# Kasli-SOC_SFP.net
KiCad netlist of a schematic drawn in Altium Designer
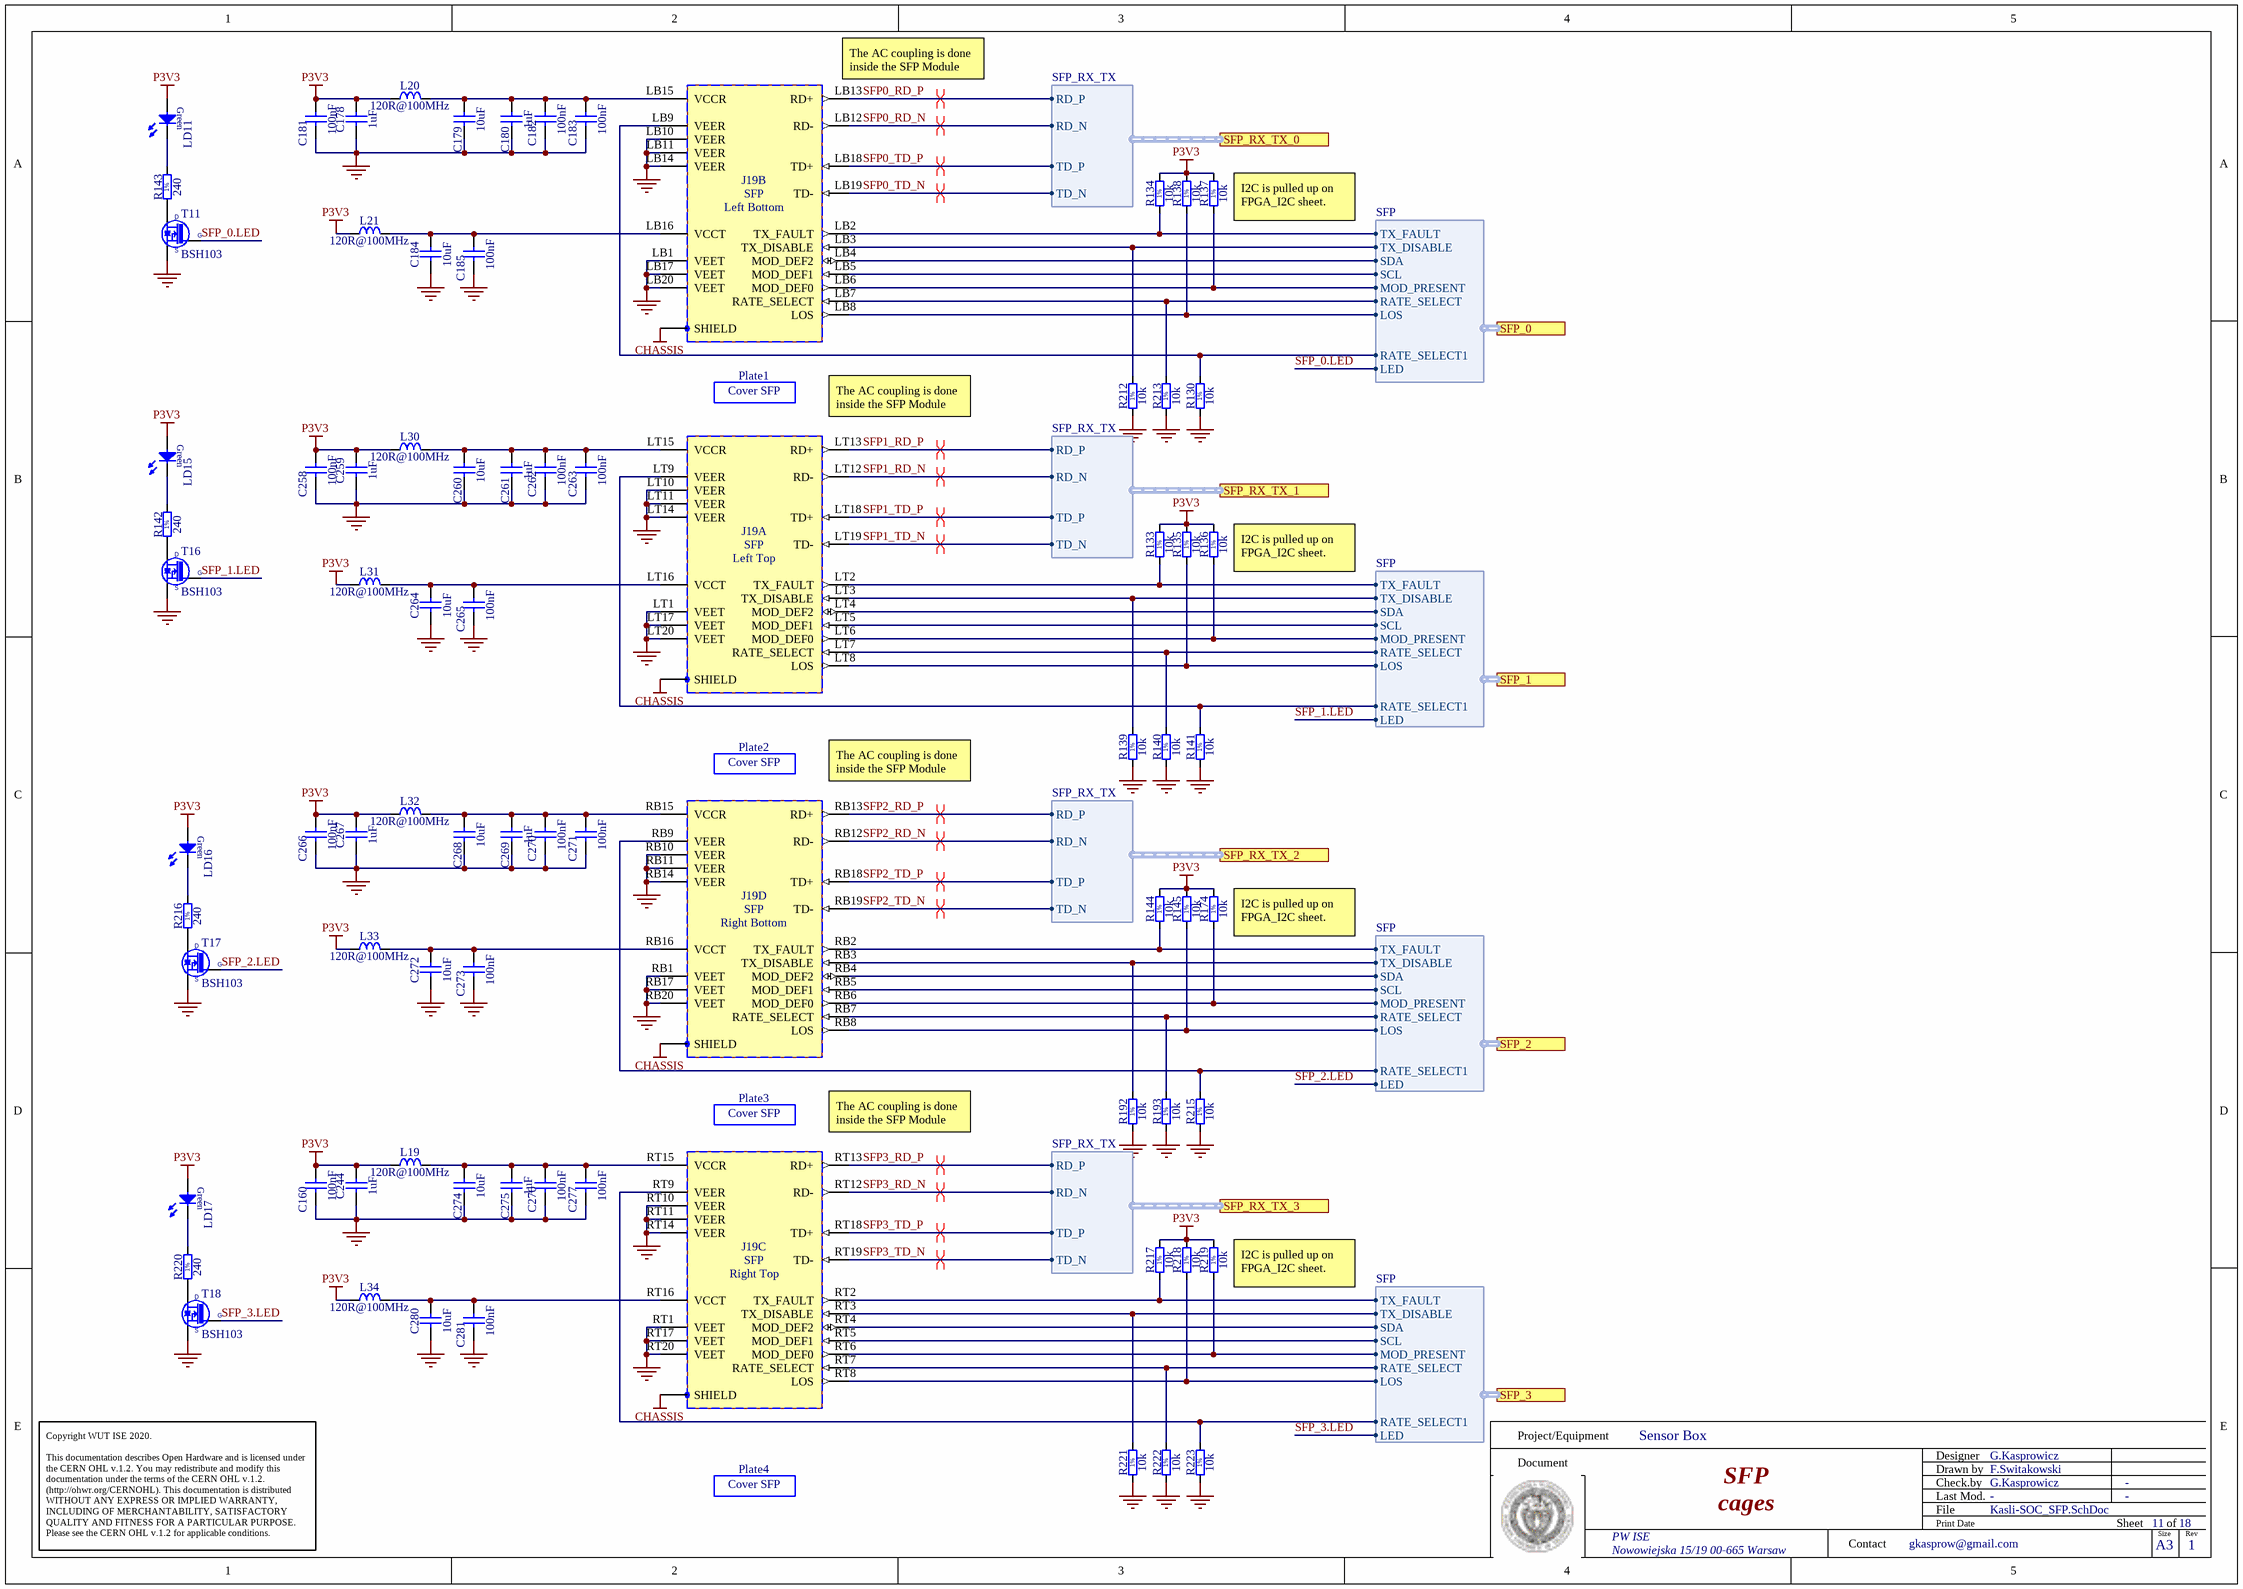
[diagram p0: Kasli-SOC_SFP.SchDoc]

(export (version "E")
  (design (tool "Eeschema 10.0.6"))
  (components
    (comp (ref "C160")
      (value "100nF")
      (footprint "CAPC1005X55N")
      (description "Non-polarised capacitor")
      (fields
        (field (name "PART NUMBER") "CC0402_100NF_16V_10%_X7R")
        (field (name "VOLTAGE") "16V")
        (field (name "AUTHOR") "CERN DEM JLC")
      )
      (libsource (lib "Capacitors") (part "Capacitor - non polarized"))
    )
    (comp (ref "C178")
      (value "1uF")
      (footprint "CAPC1005X55N")
      (description "Non-polarised capacitor")
      (fields
        (field (name "PART NUMBER") "CC0402_1UF_16V_10%_X5R")
        (field (name "VOLTAGE") "16V")
        (field (name "AUTHOR") "CERN DEM JLC")
      )
      (libsource (lib "Capacitors") (part "Capacitor - non polarized"))
    )
    (comp (ref "C179")
      (value "10uF")
      (footprint "CAPC2012X95N")
      (description "Non-polarised capacitor")
      (fields
        (field (name "PART NUMBER") "CC0805_10UF_25V_10%_X5R")
        (field (name "VOLTAGE") "25V")
        (field (name "AUTHOR") "CERN DEM JLC")
      )
      (libsource (lib "Capacitors") (part "Capacitor - non polarized"))
    )
    (comp (ref "C180")
      (value "1uF")
      (footprint "CAPC1005X55N")
      (description "Non-polarised capacitor")
      (fields
        (field (name "PART NUMBER") "CC0402_1UF_16V_10%_X5R")
        (field (name "VOLTAGE") "16V")
        (field (name "AUTHOR") "CERN DEM JLC")
      )
      (libsource (lib "Capacitors") (part "Capacitor - non polarized"))
    )
    (comp (ref "C181")
      (value "100nF")
      (footprint "CAPC1005X55N")
      (description "Non-polarised capacitor")
      (fields
        (field (name "PART NUMBER") "CC0402_100NF_16V_10%_X7R")
        (field (name "VOLTAGE") "16V")
        (field (name "AUTHOR") "CERN DEM JLC")
      )
      (libsource (lib "Capacitors") (part "Capacitor - non polarized"))
    )
    (comp (ref "C182")
      (value "100nF")
      (footprint "CAPC1005X55N")
      (description "Non-polarised capacitor")
      (fields
        (field (name "PART NUMBER") "CC0402_100NF_16V_10%_X7R")
        (field (name "VOLTAGE") "16V")
        (field (name "AUTHOR") "CERN DEM JLC")
      )
      (libsource (lib "Capacitors") (part "Capacitor - non polarized"))
    )
    (comp (ref "C183")
      (value "100nF")
      (footprint "CAPC1005X55N")
      (description "Non-polarised capacitor")
      (fields
        (field (name "PART NUMBER") "CC0402_100NF_16V_10%_X7R")
        (field (name "VOLTAGE") "16V")
        (field (name "AUTHOR") "CERN DEM JLC")
      )
      (libsource (lib "Capacitors") (part "Capacitor - non polarized"))
    )
    (comp (ref "C184")
      (value "10uF")
      (footprint "CAPC2012X95N")
      (description "Non-polarised capacitor")
      (fields
        (field (name "PART NUMBER") "CC0805_10UF_25V_10%_X5R")
        (field (name "VOLTAGE") "25V")
        (field (name "AUTHOR") "CERN DEM JLC")
      )
      (libsource (lib "Capacitors") (part "Capacitor - non polarized"))
    )
    (comp (ref "C185")
      (value "100nF")
      (footprint "CAPC1005X55N")
      (description "Non-polarised capacitor")
      (fields
        (field (name "PART NUMBER") "CC0402_100NF_16V_10%_X7R")
        (field (name "VOLTAGE") "16V")
        (field (name "AUTHOR") "CERN DEM JLC")
      )
      (libsource (lib "Capacitors") (part "Capacitor - non polarized"))
    )
    (comp (ref "C244")
      (value "1uF")
      (footprint "CAPC1005X55N")
      (description "Non-polarised capacitor")
      (fields
        (field (name "PART NUMBER") "CC0402_1UF_16V_10%_X5R")
        (field (name "VOLTAGE") "16V")
        (field (name "AUTHOR") "CERN DEM JLC")
      )
      (libsource (lib "Capacitors") (part "Capacitor - non polarized"))
    )
    (comp (ref "C258")
      (value "100nF")
      (footprint "CAPC1005X55N")
      (description "Non-polarised capacitor")
      (fields
        (field (name "PART NUMBER") "CC0402_100NF_16V_10%_X7R")
        (field (name "VOLTAGE") "16V")
        (field (name "AUTHOR") "CERN DEM JLC")
      )
      (libsource (lib "Capacitors") (part "Capacitor - non polarized"))
    )
    (comp (ref "C259")
      (value "1uF")
      (footprint "CAPC1005X55N")
      (description "Non-polarised capacitor")
      (fields
        (field (name "PART NUMBER") "CC0402_1UF_16V_10%_X5R")
        (field (name "VOLTAGE") "16V")
        (field (name "AUTHOR") "CERN DEM JLC")
      )
      (libsource (lib "Capacitors") (part "Capacitor - non polarized"))
    )
    (comp (ref "C260")
      (value "10uF")
      (footprint "CAPC2012X95N")
      (description "Non-polarised capacitor")
      (fields
        (field (name "PART NUMBER") "CC0805_10UF_25V_10%_X5R")
        (field (name "VOLTAGE") "25V")
        (field (name "AUTHOR") "CERN DEM JLC")
      )
      (libsource (lib "Capacitors") (part "Capacitor - non polarized"))
    )
    (comp (ref "C261")
      (value "1uF")
      (footprint "CAPC1005X55N")
      (description "Non-polarised capacitor")
      (fields
        (field (name "PART NUMBER") "CC0402_1UF_16V_10%_X5R")
        (field (name "VOLTAGE") "16V")
        (field (name "AUTHOR") "CERN DEM JLC")
      )
      (libsource (lib "Capacitors") (part "Capacitor - non polarized"))
    )
    (comp (ref "C262")
      (value "100nF")
      (footprint "CAPC1005X55N")
      (description "Non-polarised capacitor")
      (fields
        (field (name "PART NUMBER") "CC0402_100NF_16V_10%_X7R")
        (field (name "VOLTAGE") "16V")
        (field (name "AUTHOR") "CERN DEM JLC")
      )
      (libsource (lib "Capacitors") (part "Capacitor - non polarized"))
    )
    (comp (ref "C263")
      (value "100nF")
      (footprint "CAPC1005X55N")
      (description "Non-polarised capacitor")
      (fields
        (field (name "PART NUMBER") "CC0402_100NF_16V_10%_X7R")
        (field (name "VOLTAGE") "16V")
        (field (name "AUTHOR") "CERN DEM JLC")
      )
      (libsource (lib "Capacitors") (part "Capacitor - non polarized"))
    )
    (comp (ref "C264")
      (value "10uF")
      (footprint "CAPC2012X95N")
      (description "Non-polarised capacitor")
      (fields
        (field (name "PART NUMBER") "CC0805_10UF_25V_10%_X5R")
        (field (name "VOLTAGE") "25V")
        (field (name "AUTHOR") "CERN DEM JLC")
      )
      (libsource (lib "Capacitors") (part "Capacitor - non polarized"))
    )
    (comp (ref "C265")
      (value "100nF")
      (footprint "CAPC1005X55N")
      (description "Non-polarised capacitor")
      (fields
        (field (name "PART NUMBER") "CC0402_100NF_16V_10%_X7R")
        (field (name "VOLTAGE") "16V")
        (field (name "AUTHOR") "CERN DEM JLC")
      )
      (libsource (lib "Capacitors") (part "Capacitor - non polarized"))
    )
    (comp (ref "C266")
      (value "100nF")
      (footprint "CAPC1005X55N")
      (description "Non-polarised capacitor")
      (fields
        (field (name "PART NUMBER") "CC0402_100NF_16V_10%_X7R")
        (field (name "VOLTAGE") "16V")
        (field (name "AUTHOR") "CERN DEM JLC")
      )
      (libsource (lib "Capacitors") (part "Capacitor - non polarized"))
    )
    (comp (ref "C267")
      (value "1uF")
      (footprint "CAPC1005X55N")
      (description "Non-polarised capacitor")
      (fields
        (field (name "PART NUMBER") "CC0402_1UF_16V_10%_X5R")
        (field (name "VOLTAGE") "16V")
        (field (name "AUTHOR") "CERN DEM JLC")
      )
      (libsource (lib "Capacitors") (part "Capacitor - non polarized"))
    )
    (comp (ref "C268")
      (value "10uF")
      (footprint "CAPC2012X95N")
      (description "Non-polarised capacitor")
      (fields
        (field (name "PART NUMBER") "CC0805_10UF_25V_10%_X5R")
        (field (name "VOLTAGE") "25V")
        (field (name "AUTHOR") "CERN DEM JLC")
      )
      (libsource (lib "Capacitors") (part "Capacitor - non polarized"))
    )
    (comp (ref "C269")
      (value "1uF")
      (footprint "CAPC1005X55N")
      (description "Non-polarised capacitor")
      (fields
        (field (name "PART NUMBER") "CC0402_1UF_16V_10%_X5R")
        (field (name "VOLTAGE") "16V")
        (field (name "AUTHOR") "CERN DEM JLC")
      )
      (libsource (lib "Capacitors") (part "Capacitor - non polarized"))
    )
    (comp (ref "C270")
      (value "100nF")
      (footprint "CAPC1005X55N")
      (description "Non-polarised capacitor")
      (fields
        (field (name "PART NUMBER") "CC0402_100NF_16V_10%_X7R")
        (field (name "VOLTAGE") "16V")
        (field (name "AUTHOR") "CERN DEM JLC")
      )
      (libsource (lib "Capacitors") (part "Capacitor - non polarized"))
    )
    (comp (ref "C271")
      (value "100nF")
      (footprint "CAPC1005X55N")
      (description "Non-polarised capacitor")
      (fields
        (field (name "PART NUMBER") "CC0402_100NF_16V_10%_X7R")
        (field (name "VOLTAGE") "16V")
        (field (name "AUTHOR") "CERN DEM JLC")
      )
      (libsource (lib "Capacitors") (part "Capacitor - non polarized"))
    )
    (comp (ref "C272")
      (value "10uF")
      (footprint "CAPC2012X95N")
      (description "Non-polarised capacitor")
      (fields
        (field (name "PART NUMBER") "CC0805_10UF_25V_10%_X5R")
        (field (name "VOLTAGE") "25V")
        (field (name "AUTHOR") "CERN DEM JLC")
      )
      (libsource (lib "Capacitors") (part "Capacitor - non polarized"))
    )
    (comp (ref "C273")
      (value "100nF")
      (footprint "CAPC1005X55N")
      (description "Non-polarised capacitor")
      (fields
        (field (name "PART NUMBER") "CC0402_100NF_16V_10%_X7R")
        (field (name "VOLTAGE") "16V")
        (field (name "AUTHOR") "CERN DEM JLC")
      )
      (libsource (lib "Capacitors") (part "Capacitor - non polarized"))
    )
    (comp (ref "C274")
      (value "10uF")
      (footprint "CAPC2012X95N")
      (description "Non-polarised capacitor")
      (fields
        (field (name "PART NUMBER") "CC0805_10UF_25V_10%_X5R")
        (field (name "VOLTAGE") "25V")
        (field (name "AUTHOR") "CERN DEM JLC")
      )
      (libsource (lib "Capacitors") (part "Capacitor - non polarized"))
    )
    (comp (ref "C275")
      (value "1uF")
      (footprint "CAPC1005X55N")
      (description "Non-polarised capacitor")
      (fields
        (field (name "PART NUMBER") "CC0402_1UF_16V_10%_X5R")
        (field (name "VOLTAGE") "16V")
        (field (name "AUTHOR") "CERN DEM JLC")
      )
      (libsource (lib "Capacitors") (part "Capacitor - non polarized"))
    )
    (comp (ref "C276")
      (value "100nF")
      (footprint "CAPC1005X55N")
      (description "Non-polarised capacitor")
      (fields
        (field (name "PART NUMBER") "CC0402_100NF_16V_10%_X7R")
        (field (name "VOLTAGE") "16V")
        (field (name "AUTHOR") "CERN DEM JLC")
      )
      (libsource (lib "Capacitors") (part "Capacitor - non polarized"))
    )
    (comp (ref "C277")
      (value "100nF")
      (footprint "CAPC1005X55N")
      (description "Non-polarised capacitor")
      (fields
        (field (name "PART NUMBER") "CC0402_100NF_16V_10%_X7R")
        (field (name "VOLTAGE") "16V")
        (field (name "AUTHOR") "CERN DEM JLC")
      )
      (libsource (lib "Capacitors") (part "Capacitor - non polarized"))
    )
    (comp (ref "C280")
      (value "10uF")
      (footprint "CAPC2012X95N")
      (description "Non-polarised capacitor")
      (fields
        (field (name "PART NUMBER") "CC0805_10UF_25V_10%_X5R")
        (field (name "VOLTAGE") "25V")
        (field (name "AUTHOR") "CERN DEM JLC")
      )
      (libsource (lib "Capacitors") (part "Capacitor - non polarized"))
    )
    (comp (ref "C281")
      (value "100nF")
      (footprint "CAPC1005X55N")
      (description "Non-polarised capacitor")
      (fields
        (field (name "PART NUMBER") "CC0402_100NF_16V_10%_X7R")
        (field (name "VOLTAGE") "16V")
        (field (name "AUTHOR") "CERN DEM JLC")
      )
      (libsource (lib "Capacitors") (part "Capacitor - non polarized"))
    )
    (comp (ref "J19")
      (value "SFP")
      (footprint "AMPHENOL_UE78B212700321")
      (description "20 Position SFP  Connector (Small Form-factor Pluggable)")
      (fields
        (field (name "PART NUMBER") "AMPHENOL_UE78B212700321")
        (field (name "MANUFACTURER") "AMPHENOL")
        (field (name "AUTHOR") "CERN DEM BC")
      )
      (libsource (lib "Connectors") (part "SFP 2x2 +Cage"))
    )
    (comp (ref "L19")
      (value "120R@100MHz")
      (footprint "INDC1608X65N")
      (description "Inductor")
      (fields
        (field (name "PART NUMBER") "IND0603_MURATA_BLM18SG121TN1D")
        (field (name "POWER") "3A")
        (field (name "AUTHOR") "CERN DEM JLC")
      )
      (libsource (lib "Inductors & Transformers") (part "Inductor"))
    )
    (comp (ref "L20")
      (value "120R@100MHz")
      (footprint "INDC1608X65N")
      (description "Inductor")
      (fields
        (field (name "PART NUMBER") "IND0603_MURATA_BLM18SG121TN1D")
        (field (name "POWER") "3A")
        (field (name "AUTHOR") "CERN DEM JLC")
      )
      (libsource (lib "Inductors & Transformers") (part "Inductor"))
    )
    (comp (ref "L21")
      (value "120R@100MHz")
      (footprint "INDC1608X65N")
      (description "Inductor")
      (fields
        (field (name "PART NUMBER") "IND0603_MURATA_BLM18SG121TN1D")
        (field (name "POWER") "3A")
        (field (name "AUTHOR") "CERN DEM JLC")
      )
      (libsource (lib "Inductors & Transformers") (part "Inductor"))
    )
    (comp (ref "L30")
      (value "120R@100MHz")
      (footprint "INDC1608X65N")
      (description "Inductor")
      (fields
        (field (name "PART NUMBER") "IND0603_MURATA_BLM18SG121TN1D")
        (field (name "POWER") "3A")
        (field (name "AUTHOR") "CERN DEM JLC")
      )
      (libsource (lib "Inductors & Transformers") (part "Inductor"))
    )
    (comp (ref "L31")
      (value "120R@100MHz")
      (footprint "INDC1608X65N")
      (description "Inductor")
      (fields
        (field (name "PART NUMBER") "IND0603_MURATA_BLM18SG121TN1D")
        (field (name "POWER") "3A")
        (field (name "AUTHOR") "CERN DEM JLC")
      )
      (libsource (lib "Inductors & Transformers") (part "Inductor"))
    )
    (comp (ref "L32")
      (value "120R@100MHz")
      (footprint "INDC1608X65N")
      (description "Inductor")
      (fields
        (field (name "PART NUMBER") "IND0603_MURATA_BLM18SG121TN1D")
        (field (name "POWER") "3A")
        (field (name "AUTHOR") "CERN DEM JLC")
      )
      (libsource (lib "Inductors & Transformers") (part "Inductor"))
    )
    (comp (ref "L33")
      (value "120R@100MHz")
      (footprint "INDC1608X65N")
      (description "Inductor")
      (fields
        (field (name "PART NUMBER") "IND0603_MURATA_BLM18SG121TN1D")
        (field (name "POWER") "3A")
        (field (name "AUTHOR") "CERN DEM JLC")
      )
      (libsource (lib "Inductors & Transformers") (part "Inductor"))
    )
    (comp (ref "L34")
      (value "120R@100MHz")
      (footprint "INDC1608X65N")
      (description "Inductor")
      (fields
        (field (name "PART NUMBER") "IND0603_MURATA_BLM18SG121TN1D")
        (field (name "POWER") "3A")
        (field (name "AUTHOR") "CERN DEM JLC")
      )
      (libsource (lib "Inductors & Transformers") (part "Inductor"))
    )
    (comp (ref "LD11")
      (value "Green")
      (footprint "LED_AVAGO_HSME-C120")
      (description "LED Green 1C 2A")
      (fields
        (field (name "PART NUMBER") "LED_AVAGO_HSME-C120")
        (field (name "MANUFACTURER") "AVAGO TECHNOLOGIES")
        (field (name "AUTHOR") "CERN DEM JMW")
      )
      (libsource (lib "ICs And Semiconductors") (part "LED Green 1C 2A"))
    )
    (comp (ref "LD15")
      (value "Green")
      (footprint "LED_AVAGO_HSME-C120")
      (description "LED Green 1C 2A")
      (fields
        (field (name "PART NUMBER") "LED_AVAGO_HSME-C120")
        (field (name "MANUFACTURER") "AVAGO TECHNOLOGIES")
        (field (name "AUTHOR") "CERN DEM JMW")
      )
      (libsource (lib "ICs And Semiconductors") (part "LED Green 1C 2A"))
    )
    (comp (ref "LD16")
      (value "Green")
      (footprint "LED_AVAGO_HSME-C120")
      (description "LED Green 1C 2A")
      (fields
        (field (name "PART NUMBER") "LED_AVAGO_HSME-C120")
        (field (name "MANUFACTURER") "AVAGO TECHNOLOGIES")
        (field (name "AUTHOR") "CERN DEM JMW")
      )
      (libsource (lib "ICs And Semiconductors") (part "LED Green 1C 2A"))
    )
    (comp (ref "LD17")
      (value "Green")
      (footprint "LED_AVAGO_HSME-C120")
      (description "LED Green 1C 2A")
      (fields
        (field (name "PART NUMBER") "LED_AVAGO_HSME-C120")
        (field (name "MANUFACTURER") "AVAGO TECHNOLOGIES")
        (field (name "AUTHOR") "CERN DEM JMW")
      )
      (libsource (lib "ICs And Semiconductors") (part "LED Green 1C 2A"))
    )
    (comp (ref "Plate1")
      (value "Cover SFP")
      (footprint "AMPHENOL_U77A11108000P")
      (description "Plastic Dust Cover SFP Cage")
      (fields
        (field (name "PART NUMBER") "AMPHENOL_U77A11108000P")
        (field (name "MANUFACTURER") "AMPHENOL")
        (field (name "AUTHOR") "CERN DEM BC")
      )
      (libsource (lib "Eletro-mechanical") (part "SFP Cover No Pin"))
    )
    (comp (ref "Plate2")
      (value "Cover SFP")
      (footprint "AMPHENOL_U77A11108000P")
      (description "Plastic Dust Cover SFP Cage")
      (fields
        (field (name "MANUFACTURER") "AMPHENOL")
        (field (name "MANUFACTURER PART NUMBER") "U77A11108000P")
        (field (name "AUTHOR") "CERN DEM BC")
      )
      (libsource (lib "Eletro-mechanical") (part "SFP Cover No Pin"))
    )
    (comp (ref "Plate3")
      (value "Cover SFP")
      (footprint "AMPHENOL_U77A11108000P")
      (description "Plastic Dust Cover SFP Cage")
      (fields
        (field (name "MANUFACTURER") "AMPHENOL")
        (field (name "MANUFACTURER PART NUMBER") "U77A11108000P")
        (field (name "AUTHOR") "CERN DEM BC")
      )
      (libsource (lib "Eletro-mechanical") (part "SFP Cover No Pin"))
    )
    (comp (ref "Plate4")
      (value "Cover SFP")
      (footprint "AMPHENOL_U77A11108000P")
      (description "Plastic Dust Cover SFP Cage")
      (fields
        (field (name "MANUFACTURER") "AMPHENOL")
        (field (name "MANUFACTURER PART NUMBER") "U77A11108000P")
        (field (name "AUTHOR") "CERN DEM BC")
      )
      (libsource (lib "Eletro-mechanical") (part "SFP Cover No Pin"))
    )
    (comp (ref "R130")
      (value "10k")
      (footprint "RESC1005X40N")
      (description "Resistor - 1%")
      (fields
        (field (name "PART NUMBER") "R0402_10K_1%_0.0625W_100PPM")
        (field (name "POWER") "0.0625W")
        (field (name "AUTHOR") "CERN DEM JLC")
      )
      (libsource (lib "Resistors") (part "Resistor - 1%"))
    )
    (comp (ref "R133")
      (value "10k")
      (footprint "RESC1005X40N")
      (description "Resistor - 1%")
      (fields
        (field (name "PART NUMBER") "R0402_10K_1%_0.0625W_100PPM")
        (field (name "POWER") "0.0625W")
        (field (name "AUTHOR") "CERN DEM JLC")
      )
      (libsource (lib "Resistors") (part "Resistor - 1%"))
    )
    (comp (ref "R134")
      (value "10k")
      (footprint "RESC1005X40N")
      (description "Resistor - 1%")
      (fields
        (field (name "PART NUMBER") "R0402_10K_1%_0.0625W_100PPM")
        (field (name "POWER") "0.0625W")
        (field (name "AUTHOR") "CERN DEM JLC")
      )
      (libsource (lib "Resistors") (part "Resistor - 1%"))
    )
    (comp (ref "R135")
      (value "10k")
      (footprint "RESC1005X40N")
      (description "Resistor - 1%")
      (fields
        (field (name "PART NUMBER") "R0402_10K_1%_0.0625W_100PPM")
        (field (name "POWER") "0.0625W")
        (field (name "AUTHOR") "CERN DEM JLC")
      )
      (libsource (lib "Resistors") (part "Resistor - 1%"))
    )
    (comp (ref "R136")
      (value "10k")
      (footprint "RESC1005X40N")
      (description "Resistor - 1%")
      (fields
        (field (name "PART NUMBER") "R0402_10K_1%_0.0625W_100PPM")
        (field (name "POWER") "0.0625W")
        (field (name "AUTHOR") "CERN DEM JLC")
      )
      (libsource (lib "Resistors") (part "Resistor - 1%"))
    )
    (comp (ref "R137")
      (value "10k")
      (footprint "RESC1005X40N")
      (description "Resistor - 1%")
      (fields
        (field (name "PART NUMBER") "R0402_10K_1%_0.0625W_100PPM")
        (field (name "POWER") "0.0625W")
        (field (name "AUTHOR") "CERN DEM JLC")
      )
      (libsource (lib "Resistors") (part "Resistor - 1%"))
    )
    (comp (ref "R138")
      (value "10k")
      (footprint "RESC1005X40N")
      (description "Resistor - 1%")
      (fields
        (field (name "PART NUMBER") "R0402_10K_1%_0.0625W_100PPM")
        (field (name "POWER") "0.0625W")
        (field (name "AUTHOR") "CERN DEM JLC")
      )
      (libsource (lib "Resistors") (part "Resistor - 1%"))
    )
    (comp (ref "R139")
      (value "10k")
      (footprint "RESC1005X40N")
      (description "Resistor - 1%")
      (fields
        (field (name "PART NUMBER") "R0402_10K_1%_0.0625W_100PPM")
        (field (name "POWER") "0.0625W")
        (field (name "AUTHOR") "CERN DEM JLC")
      )
      (libsource (lib "Resistors") (part "Resistor - 1%"))
    )
    (comp (ref "R140")
      (value "10k")
      (footprint "RESC1005X40N")
      (description "Resistor - 1%")
      (fields
        (field (name "PART NUMBER") "R0402_10K_1%_0.0625W_100PPM")
        (field (name "POWER") "0.0625W")
        (field (name "AUTHOR") "CERN DEM JLC")
      )
      (libsource (lib "Resistors") (part "Resistor - 1%"))
    )
    (comp (ref "R141")
      (value "10k")
      (footprint "RESC1005X40N")
      (description "Resistor - 1%")
      (fields
        (field (name "PART NUMBER") "R0402_10K_1%_0.0625W_100PPM")
        (field (name "POWER") "0.0625W")
        (field (name "AUTHOR") "CERN DEM JLC")
      )
      (libsource (lib "Resistors") (part "Resistor - 1%"))
    )
    (comp (ref "R142")
      (value "240")
      (footprint "RESC1005X40N")
      (description "Resistor - 1%")
      (fields
        (field (name "PART NUMBER") "R0402_240R_1%_0.0625W_100PPM")
        (field (name "POWER") "0.0625W")
        (field (name "AUTHOR") "CERN DEM JLC")
      )
      (libsource (lib "Resistors") (part "Resistor - 1%"))
    )
    (comp (ref "R143")
      (value "240")
      (footprint "RESC1005X40N")
      (description "Resistor - 1%")
      (fields
        (field (name "PART NUMBER") "R0402_240R_1%_0.0625W_100PPM")
        (field (name "POWER") "0.0625W")
        (field (name "AUTHOR") "CERN DEM JLC")
      )
      (libsource (lib "Resistors") (part "Resistor - 1%"))
    )
    (comp (ref "R144")
      (value "10k")
      (footprint "RESC1005X40N")
      (description "Resistor - 1%")
      (fields
        (field (name "PART NUMBER") "R0402_10K_1%_0.0625W_100PPM")
        (field (name "POWER") "0.0625W")
        (field (name "AUTHOR") "CERN DEM JLC")
      )
      (libsource (lib "Resistors") (part "Resistor - 1%"))
    )
    (comp (ref "R145")
      (value "10k")
      (footprint "RESC1005X40N")
      (description "Resistor - 1%")
      (fields
        (field (name "PART NUMBER") "R0402_10K_1%_0.0625W_100PPM")
        (field (name "POWER") "0.0625W")
        (field (name "AUTHOR") "CERN DEM JLC")
      )
      (libsource (lib "Resistors") (part "Resistor - 1%"))
    )
    (comp (ref "R174")
      (value "10k")
      (footprint "RESC1005X40N")
      (description "Resistor - 1%")
      (fields
        (field (name "PART NUMBER") "R0402_10K_1%_0.0625W_100PPM")
        (field (name "POWER") "0.0625W")
        (field (name "AUTHOR") "CERN DEM JLC")
      )
      (libsource (lib "Resistors") (part "Resistor - 1%"))
    )
    (comp (ref "R192")
      (value "10k")
      (footprint "RESC1005X40N")
      (description "Resistor - 1%")
      (fields
        (field (name "PART NUMBER") "R0402_10K_1%_0.0625W_100PPM")
        (field (name "POWER") "0.0625W")
        (field (name "AUTHOR") "CERN DEM JLC")
      )
      (libsource (lib "Resistors") (part "Resistor - 1%"))
    )
    (comp (ref "R193")
      (value "10k")
      (footprint "RESC1005X40N")
      (description "Resistor - 1%")
      (fields
        (field (name "PART NUMBER") "R0402_10K_1%_0.0625W_100PPM")
        (field (name "POWER") "0.0625W")
        (field (name "AUTHOR") "CERN DEM JLC")
      )
      (libsource (lib "Resistors") (part "Resistor - 1%"))
    )
    (comp (ref "R212")
      (value "10k")
      (footprint "RESC1005X40N")
      (description "Resistor - 1%")
      (fields
        (field (name "PART NUMBER") "R0402_10K_1%_0.0625W_100PPM")
        (field (name "POWER") "0.0625W")
        (field (name "AUTHOR") "CERN DEM JLC")
      )
      (libsource (lib "Resistors") (part "Resistor - 1%"))
    )
    (comp (ref "R213")
      (value "10k")
      (footprint "RESC1005X40N")
      (description "Resistor - 1%")
      (fields
        (field (name "PART NUMBER") "R0402_10K_1%_0.0625W_100PPM")
        (field (name "POWER") "0.0625W")
        (field (name "AUTHOR") "CERN DEM JLC")
      )
      (libsource (lib "Resistors") (part "Resistor - 1%"))
    )
    (comp (ref "R215")
      (value "10k")
      (footprint "RESC1005X40N")
      (description "Resistor - 1%")
      (fields
        (field (name "PART NUMBER") "R0402_10K_1%_0.0625W_100PPM")
        (field (name "POWER") "0.0625W")
        (field (name "AUTHOR") "CERN DEM JLC")
      )
      (libsource (lib "Resistors") (part "Resistor - 1%"))
    )
    (comp (ref "R216")
      (value "240")
      (footprint "RESC1005X40N")
      (description "Resistor - 1%")
      (fields
        (field (name "PART NUMBER") "R0402_240R_1%_0.0625W_100PPM")
        (field (name "POWER") "0.0625W")
        (field (name "AUTHOR") "CERN DEM JLC")
      )
      (libsource (lib "Resistors") (part "Resistor - 1%"))
    )
    (comp (ref "R217")
      (value "10k")
      (footprint "RESC1005X40N")
      (description "Resistor - 1%")
      (fields
        (field (name "PART NUMBER") "R0402_10K_1%_0.0625W_100PPM")
        (field (name "POWER") "0.0625W")
        (field (name "AUTHOR") "CERN DEM JLC")
      )
      (libsource (lib "Resistors") (part "Resistor - 1%"))
    )
    (comp (ref "R218")
      (value "10k")
      (footprint "RESC1005X40N")
      (description "Resistor - 1%")
      (fields
        (field (name "PART NUMBER") "R0402_10K_1%_0.0625W_100PPM")
        (field (name "POWER") "0.0625W")
        (field (name "AUTHOR") "CERN DEM JLC")
      )
      (libsource (lib "Resistors") (part "Resistor - 1%"))
    )
    (comp (ref "R219")
      (value "10k")
      (footprint "RESC1005X40N")
      (description "Resistor - 1%")
      (fields
        (field (name "PART NUMBER") "R0402_10K_1%_0.0625W_100PPM")
        (field (name "POWER") "0.0625W")
        (field (name "AUTHOR") "CERN DEM JLC")
      )
      (libsource (lib "Resistors") (part "Resistor - 1%"))
    )
    (comp (ref "R220")
      (value "240")
      (footprint "RESC1005X40N")
      (description "Resistor - 1%")
      (fields
        (field (name "PART NUMBER") "R0402_240R_1%_0.0625W_100PPM")
        (field (name "POWER") "0.0625W")
        (field (name "AUTHOR") "CERN DEM JLC")
      )
      (libsource (lib "Resistors") (part "Resistor - 1%"))
    )
    (comp (ref "R221")
      (value "10k")
      (footprint "RESC1005X40N")
      (description "Resistor - 1%")
      (fields
        (field (name "PART NUMBER") "R0402_10K_1%_0.0625W_100PPM")
        (field (name "POWER") "0.0625W")
        (field (name "AUTHOR") "CERN DEM JLC")
      )
      (libsource (lib "Resistors") (part "Resistor - 1%"))
    )
    (comp (ref "R222")
      (value "10k")
      (footprint "RESC1005X40N")
      (description "Resistor - 1%")
      (fields
        (field (name "PART NUMBER") "R0402_10K_1%_0.0625W_100PPM")
        (field (name "POWER") "0.0625W")
        (field (name "AUTHOR") "CERN DEM JLC")
      )
      (libsource (lib "Resistors") (part "Resistor - 1%"))
    )
    (comp (ref "R223")
      (value "10k")
      (footprint "RESC1005X40N")
      (description "Resistor - 1%")
      (fields
        (field (name "PART NUMBER") "R0402_10K_1%_0.0625W_100PPM")
        (field (name "POWER") "0.0625W")
        (field (name "AUTHOR") "CERN DEM JLC")
      )
      (libsource (lib "Resistors") (part "Resistor - 1%"))
    )
    (comp (ref "T11")
      (value "BSH103")
      (footprint "SOT95P230X110-3N")
      (description "N-CHANNEL MOSFET WITH DIODE")
      (fields (field (name "MANUFACTURER") "NEXPERIA") (field (name "AUTHOR") "CERN DEM JLC"))
      (libsource (lib "ICs And Semiconductors") (part "N-MOSFET-D 1G 2S 3D"))
    )
    (comp (ref "T16")
      (value "BSH103")
      (footprint "SOT95P230X110-3N")
      (description "N-CHANNEL MOSFET WITH DIODE")
      (fields (field (name "MANUFACTURER") "NEXPERIA") (field (name "AUTHOR") "CERN DEM JLC"))
      (libsource (lib "ICs And Semiconductors") (part "N-MOSFET-D 1G 2S 3D"))
    )
    (comp (ref "T17")
      (value "BSH103")
      (footprint "SOT95P230X110-3N")
      (description "N-CHANNEL MOSFET WITH DIODE")
      (fields (field (name "MANUFACTURER") "NEXPERIA") (field (name "AUTHOR") "CERN DEM JLC"))
      (libsource (lib "ICs And Semiconductors") (part "N-MOSFET-D 1G 2S 3D"))
    )
    (comp (ref "T18")
      (value "BSH103")
      (footprint "SOT95P230X110-3N")
      (description "N-CHANNEL MOSFET WITH DIODE")
      (fields (field (name "MANUFACTURER") "NEXPERIA") (field (name "AUTHOR") "CERN DEM JLC"))
      (libsource (lib "ICs And Semiconductors") (part "N-MOSFET-D 1G 2S 3D"))
    )
  )
  (nets
    (net (code "3") (name "/SFP0_RD_N") (class "Default")
      (node (ref "J19") (pin "LB12") (pinfunction "RD-_LB12") (pintype "output"))
    )
    (net (code "4") (name "/SFP0_RD_P") (class "Default")
      (node (ref "J19") (pin "LB13") (pinfunction "RD+_LB13") (pintype "output"))
    )
    (net (code "5") (name "/SFP0_TD_N") (class "Default")
      (node (ref "J19") (pin "LB19") (pinfunction "TD-_LB19") (pintype "input"))
    )
    (net (code "6") (name "/SFP0_TD_P") (class "Default")
      (node (ref "J19") (pin "LB18") (pinfunction "TD+_LB18") (pintype "input"))
    )
    (net (code "7") (name "/SFP1_RD_N") (class "Default")
      (node (ref "J19") (pin "LT12") (pinfunction "RD-_LT12") (pintype "output"))
    )
    (net (code "8") (name "/SFP1_RD_P") (class "Default")
      (node (ref "J19") (pin "LT13") (pinfunction "RD+_LT13") (pintype "output"))
    )
    (net (code "9") (name "/SFP1_TD_N") (class "Default")
      (node (ref "J19") (pin "LT19") (pinfunction "TD-_LT19") (pintype "input"))
    )
    (net (code "10") (name "/SFP1_TD_P") (class "Default")
      (node (ref "J19") (pin "LT18") (pinfunction "TD+_LT18") (pintype "input"))
    )
    (net (code "11") (name "/SFP2_RD_N") (class "Default")
      (node (ref "J19") (pin "RB12") (pinfunction "RD-_RB12") (pintype "output"))
    )
    (net (code "12") (name "/SFP2_RD_P") (class "Default")
      (node (ref "J19") (pin "RB13") (pinfunction "RD+_RB13") (pintype "output"))
    )
    (net (code "13") (name "/SFP2_TD_N") (class "Default")
      (node (ref "J19") (pin "RB19") (pinfunction "TD-_RB19") (pintype "input"))
    )
    (net (code "14") (name "/SFP2_TD_P") (class "Default")
      (node (ref "J19") (pin "RB18") (pinfunction "TD+_RB18") (pintype "input"))
    )
    (net (code "15") (name "/SFP3_RD_N") (class "Default")
      (node (ref "J19") (pin "RT12") (pinfunction "RD-_RT12") (pintype "output"))
    )
    (net (code "16") (name "/SFP3_RD_P") (class "Default")
      (node (ref "J19") (pin "RT13") (pinfunction "RD+_RT13") (pintype "output"))
    )
    (net (code "17") (name "/SFP3_TD_N") (class "Default")
      (node (ref "J19") (pin "RT19") (pinfunction "TD-_RT19") (pintype "input"))
    )
    (net (code "18") (name "/SFP3_TD_P") (class "Default")
      (node (ref "J19") (pin "RT18") (pinfunction "TD+_RT18") (pintype "input"))
    )
    (net (code "19") (name "/SFP_0.LED") (class "Default")
      (node (ref "T11") (pin "1") (pinfunction "G_1") (pintype "passive"))
    )
    (net (code "20") (name "/SFP_1.LED") (class "Default")
      (node (ref "T16") (pin "1") (pinfunction "G_1") (pintype "passive"))
    )
    (net (code "21") (name "/SFP_2.LED") (class "Default")
      (node (ref "T17") (pin "1") (pinfunction "G_1") (pintype "passive"))
    )
    (net (code "22") (name "/SFP_3.LED") (class "Default")
      (node (ref "T18") (pin "1") (pinfunction "G_1") (pintype "passive"))
    )
    (net (code "25") (name "CHASSIS") (class "Default")
      (node (ref "J19") (pin "SHIELD") (pinfunction "SHIELD_SHIELD") (pintype "power_in"))
    )
    (net (code "26") (name "GND") (class "Default")
      (node (ref "C160") (pin "1") (pinfunction "1_1") (pintype "passive"))
      (node (ref "C178") (pin "1") (pinfunction "1_1") (pintype "passive"))
      (node (ref "C179") (pin "1") (pinfunction "1_1") (pintype "passive"))
      (node (ref "C180") (pin "1") (pinfunction "1_1") (pintype "passive"))
      (node (ref "C181") (pin "1") (pinfunction "1_1") (pintype "passive"))
      (node (ref "C182") (pin "1") (pinfunction "1_1") (pintype "passive"))
      (node (ref "C183") (pin "1") (pinfunction "1_1") (pintype "passive"))
      (node (ref "C184") (pin "1") (pinfunction "1_1") (pintype "passive"))
      (node (ref "C185") (pin "1") (pinfunction "1_1") (pintype "passive"))
      (node (ref "C244") (pin "1") (pinfunction "1_1") (pintype "passive"))
      (node (ref "C258") (pin "1") (pinfunction "1_1") (pintype "passive"))
      (node (ref "C259") (pin "1") (pinfunction "1_1") (pintype "passive"))
      (node (ref "C260") (pin "1") (pinfunction "1_1") (pintype "passive"))
      (node (ref "C261") (pin "1") (pinfunction "1_1") (pintype "passive"))
      (node (ref "C262") (pin "1") (pinfunction "1_1") (pintype "passive"))
      (node (ref "C263") (pin "1") (pinfunction "1_1") (pintype "passive"))
      (node (ref "C264") (pin "1") (pinfunction "1_1") (pintype "passive"))
      (node (ref "C265") (pin "1") (pinfunction "1_1") (pintype "passive"))
      (node (ref "C266") (pin "1") (pinfunction "1_1") (pintype "passive"))
      (node (ref "C267") (pin "1") (pinfunction "1_1") (pintype "passive"))
      (node (ref "C268") (pin "1") (pinfunction "1_1") (pintype "passive"))
      (node (ref "C269") (pin "1") (pinfunction "1_1") (pintype "passive"))
      (node (ref "C270") (pin "1") (pinfunction "1_1") (pintype "passive"))
      (node (ref "C271") (pin "1") (pinfunction "1_1") (pintype "passive"))
      (node (ref "C272") (pin "1") (pinfunction "1_1") (pintype "passive"))
      (node (ref "C273") (pin "1") (pinfunction "1_1") (pintype "passive"))
      (node (ref "C274") (pin "1") (pinfunction "1_1") (pintype "passive"))
      (node (ref "C275") (pin "1") (pinfunction "1_1") (pintype "passive"))
      (node (ref "C276") (pin "1") (pinfunction "1_1") (pintype "passive"))
      (node (ref "C277") (pin "1") (pinfunction "1_1") (pintype "passive"))
      (node (ref "C280") (pin "1") (pinfunction "1_1") (pintype "passive"))
      (node (ref "C281") (pin "1") (pinfunction "1_1") (pintype "passive"))
      (node (ref "J19") (pin "LB1") (pinfunction "VEET_LB1") (pintype "power_in"))
      (node (ref "J19") (pin "LB10") (pinfunction "VEER_LB10") (pintype "power_in"))
      (node (ref "J19") (pin "LB11") (pinfunction "VEER_LB11") (pintype "power_in"))
      (node (ref "J19") (pin "LB14") (pinfunction "VEER_LB14") (pintype "power_in"))
      (node (ref "J19") (pin "LB17") (pinfunction "VEET_LB17") (pintype "power_in"))
      (node (ref "J19") (pin "LB20") (pinfunction "VEET_LB20") (pintype "power_in"))
      (node (ref "J19") (pin "LT1") (pinfunction "VEET_LT1") (pintype "power_in"))
      (node (ref "J19") (pin "LT10") (pinfunction "VEER_LT10") (pintype "power_in"))
      (node (ref "J19") (pin "LT11") (pinfunction "VEER_LT11") (pintype "power_in"))
      (node (ref "J19") (pin "LT14") (pinfunction "VEER_LT14") (pintype "power_in"))
      (node (ref "J19") (pin "LT17") (pinfunction "VEET_LT17") (pintype "power_in"))
      (node (ref "J19") (pin "LT20") (pinfunction "VEET_LT20") (pintype "power_in"))
      (node (ref "J19") (pin "RB1") (pinfunction "VEET_RB1") (pintype "power_in"))
      (node (ref "J19") (pin "RB10") (pinfunction "VEER_RB10") (pintype "power_in"))
      (node (ref "J19") (pin "RB11") (pinfunction "VEER_RB11") (pintype "power_in"))
      (node (ref "J19") (pin "RB14") (pinfunction "VEER_RB14") (pintype "power_in"))
      (node (ref "J19") (pin "RB17") (pinfunction "VEET_RB17") (pintype "power_in"))
      (node (ref "J19") (pin "RB20") (pinfunction "VEET_RB20") (pintype "power_in"))
      (node (ref "J19") (pin "RT1") (pinfunction "VEET_RT1") (pintype "power_in"))
      (node (ref "J19") (pin "RT10") (pinfunction "VEER_RT10") (pintype "power_in"))
      (node (ref "J19") (pin "RT11") (pinfunction "VEER_RT11") (pintype "power_in"))
      (node (ref "J19") (pin "RT14") (pinfunction "VEER_RT14") (pintype "power_in"))
      (node (ref "J19") (pin "RT17") (pinfunction "VEET_RT17") (pintype "power_in"))
      (node (ref "J19") (pin "RT20") (pinfunction "VEET_RT20") (pintype "power_in"))
      (node (ref "R130") (pin "1") (pinfunction "1_1") (pintype "passive"))
      (node (ref "R139") (pin "1") (pinfunction "1_1") (pintype "passive"))
      (node (ref "R140") (pin "1") (pinfunction "1_1") (pintype "passive"))
      (node (ref "R141") (pin "1") (pinfunction "1_1") (pintype "passive"))
      (node (ref "R192") (pin "1") (pinfunction "1_1") (pintype "passive"))
      (node (ref "R193") (pin "1") (pinfunction "1_1") (pintype "passive"))
      (node (ref "R212") (pin "1") (pinfunction "1_1") (pintype "passive"))
      (node (ref "R213") (pin "1") (pinfunction "1_1") (pintype "passive"))
      (node (ref "R215") (pin "1") (pinfunction "1_1") (pintype "passive"))
      (node (ref "R221") (pin "1") (pinfunction "1_1") (pintype "passive"))
      (node (ref "R222") (pin "1") (pinfunction "1_1") (pintype "passive"))
      (node (ref "R223") (pin "1") (pinfunction "1_1") (pintype "passive"))
      (node (ref "T11") (pin "2") (pinfunction "S_2") (pintype "passive"))
      (node (ref "T16") (pin "2") (pinfunction "S_2") (pintype "passive"))
      (node (ref "T17") (pin "2") (pinfunction "S_2") (pintype "passive"))
      (node (ref "T18") (pin "2") (pinfunction "S_2") (pintype "passive"))
    )
    (net (code "27") (name "Net-(J19A-LOS)") (class "Default")
      (node (ref "J19") (pin "LT8") (pinfunction "LOS_LT8") (pintype "output"))
      (node (ref "R135") (pin "1") (pinfunction "1_1") (pintype "passive"))
    )
    (net (code "28") (name "Net-(J19A-MOD_DEF0)") (class "Default")
      (node (ref "J19") (pin "LT6") (pinfunction "MOD_DEF0_LT6") (pintype "output"))
      (node (ref "R136") (pin "1") (pinfunction "1_1") (pintype "passive"))
    )
    (net (code "29") (name "Net-(J19A-RATE_SELECT)") (class "Default")
      (node (ref "J19") (pin "LT7") (pinfunction "RATE_SELECT_LT7") (pintype "input"))
      (node (ref "R140") (pin "2") (pinfunction "2_2") (pintype "passive"))
    )
    (net (code "30") (name "Net-(J19A-TX_DISABLE)") (class "Default")
      (node (ref "J19") (pin "LT3") (pinfunction "TX_DISABLE_LT3") (pintype "input"))
      (node (ref "R139") (pin "2") (pinfunction "2_2") (pintype "passive"))
    )
    (net (code "31") (name "Net-(J19A-TX_FAULT)") (class "Default")
      (node (ref "J19") (pin "LT2") (pinfunction "TX_FAULT_LT2") (pintype "output"))
      (node (ref "R133") (pin "1") (pinfunction "1_1") (pintype "passive"))
    )
    (net (code "32") (name "Net-(J19A-VCCR)") (class "Default")
      (node (ref "C260") (pin "2") (pinfunction "2_2") (pintype "passive"))
      (node (ref "C261") (pin "2") (pinfunction "2_2") (pintype "passive"))
      (node (ref "C262") (pin "2") (pinfunction "2_2") (pintype "passive"))
      (node (ref "C263") (pin "2") (pinfunction "2_2") (pintype "passive"))
      (node (ref "J19") (pin "LT15") (pinfunction "VCCR_LT15") (pintype "power_in"))
      (node (ref "L30") (pin "2") (pinfunction "2_2") (pintype "passive"))
    )
    (net (code "33") (name "Net-(J19A-VCCT)") (class "Default")
      (node (ref "C264") (pin "2") (pinfunction "2_2") (pintype "passive"))
      (node (ref "C265") (pin "2") (pinfunction "2_2") (pintype "passive"))
      (node (ref "J19") (pin "LT16") (pinfunction "VCCT_LT16") (pintype "power_in"))
      (node (ref "L31") (pin "2") (pinfunction "2_2") (pintype "passive"))
    )
    (net (code "34") (name "Net-(J19A-VEER-PadLT9)") (class "Default")
      (node (ref "J19") (pin "LT9") (pinfunction "VEER_LT9") (pintype "power_in"))
      (node (ref "R141") (pin "2") (pinfunction "2_2") (pintype "passive"))
    )
    (net (code "35") (name "Net-(J19B-LOS)") (class "Default")
      (node (ref "J19") (pin "LB8") (pinfunction "LOS_LB8") (pintype "output"))
      (node (ref "R138") (pin "1") (pinfunction "1_1") (pintype "passive"))
    )
    (net (code "36") (name "Net-(J19B-MOD_DEF0)") (class "Default")
      (node (ref "J19") (pin "LB6") (pinfunction "MOD_DEF0_LB6") (pintype "output"))
      (node (ref "R137") (pin "1") (pinfunction "1_1") (pintype "passive"))
    )
    (net (code "37") (name "Net-(J19B-RATE_SELECT)") (class "Default")
      (node (ref "J19") (pin "LB7") (pinfunction "RATE_SELECT_LB7") (pintype "input"))
      (node (ref "R213") (pin "2") (pinfunction "2_2") (pintype "passive"))
    )
    (net (code "38") (name "Net-(J19B-TX_DISABLE)") (class "Default")
      (node (ref "J19") (pin "LB3") (pinfunction "TX_DISABLE_LB3") (pintype "input"))
      (node (ref "R212") (pin "2") (pinfunction "2_2") (pintype "passive"))
    )
    (net (code "39") (name "Net-(J19B-TX_FAULT)") (class "Default")
      (node (ref "J19") (pin "LB2") (pinfunction "TX_FAULT_LB2") (pintype "output"))
      (node (ref "R134") (pin "1") (pinfunction "1_1") (pintype "passive"))
    )
    (net (code "40") (name "Net-(J19B-VCCR)") (class "Default")
      (node (ref "C179") (pin "2") (pinfunction "2_2") (pintype "passive"))
      (node (ref "C180") (pin "2") (pinfunction "2_2") (pintype "passive"))
      (node (ref "C182") (pin "2") (pinfunction "2_2") (pintype "passive"))
      (node (ref "C183") (pin "2") (pinfunction "2_2") (pintype "passive"))
      (node (ref "J19") (pin "LB15") (pinfunction "VCCR_LB15") (pintype "power_in"))
      (node (ref "L20") (pin "2") (pinfunction "2_2") (pintype "passive"))
    )
    (net (code "41") (name "Net-(J19B-VCCT)") (class "Default")
      (node (ref "C184") (pin "2") (pinfunction "2_2") (pintype "passive"))
      (node (ref "C185") (pin "2") (pinfunction "2_2") (pintype "passive"))
      (node (ref "J19") (pin "LB16") (pinfunction "VCCT_LB16") (pintype "power_in"))
      (node (ref "L21") (pin "2") (pinfunction "2_2") (pintype "passive"))
    )
    (net (code "42") (name "Net-(J19B-VEER-PadLB9)") (class "Default")
      (node (ref "J19") (pin "LB9") (pinfunction "VEER_LB9") (pintype "power_in"))
      (node (ref "R130") (pin "2") (pinfunction "2_2") (pintype "passive"))
    )
    (net (code "43") (name "Net-(J19C-LOS)") (class "Default")
      (node (ref "J19") (pin "RT8") (pinfunction "LOS_RT8") (pintype "output"))
      (node (ref "R218") (pin "1") (pinfunction "1_1") (pintype "passive"))
    )
    (net (code "44") (name "Net-(J19C-MOD_DEF0)") (class "Default")
      (node (ref "J19") (pin "RT6") (pinfunction "MOD_DEF0_RT6") (pintype "output"))
      (node (ref "R219") (pin "1") (pinfunction "1_1") (pintype "passive"))
    )
    (net (code "45") (name "Net-(J19C-RATE_SELECT)") (class "Default")
      (node (ref "J19") (pin "RT7") (pinfunction "RATE_SELECT_RT7") (pintype "input"))
      (node (ref "R222") (pin "2") (pinfunction "2_2") (pintype "passive"))
    )
    (net (code "46") (name "Net-(J19C-TX_DISABLE)") (class "Default")
      (node (ref "J19") (pin "RT3") (pinfunction "TX_DISABLE_RT3") (pintype "input"))
      (node (ref "R221") (pin "2") (pinfunction "2_2") (pintype "passive"))
    )
    (net (code "47") (name "Net-(J19C-TX_FAULT)") (class "Default")
      (node (ref "J19") (pin "RT2") (pinfunction "TX_FAULT_RT2") (pintype "output"))
      (node (ref "R217") (pin "1") (pinfunction "1_1") (pintype "passive"))
    )
    (net (code "48") (name "Net-(J19C-VCCR)") (class "Default")
      (node (ref "C274") (pin "2") (pinfunction "2_2") (pintype "passive"))
      (node (ref "C275") (pin "2") (pinfunction "2_2") (pintype "passive"))
      (node (ref "C276") (pin "2") (pinfunction "2_2") (pintype "passive"))
      (node (ref "C277") (pin "2") (pinfunction "2_2") (pintype "passive"))
      (node (ref "J19") (pin "RT15") (pinfunction "VCCR_RT15") (pintype "power_in"))
      (node (ref "L19") (pin "2") (pinfunction "2_2") (pintype "passive"))
    )
    (net (code "49") (name "Net-(J19C-VCCT)") (class "Default")
      (node (ref "C280") (pin "2") (pinfunction "2_2") (pintype "passive"))
      (node (ref "C281") (pin "2") (pinfunction "2_2") (pintype "passive"))
      (node (ref "J19") (pin "RT16") (pinfunction "VCCT_RT16") (pintype "power_in"))
      (node (ref "L34") (pin "2") (pinfunction "2_2") (pintype "passive"))
    )
    (net (code "50") (name "Net-(J19C-VEER-PadRT9)") (class "Default")
      (node (ref "J19") (pin "RT9") (pinfunction "VEER_RT9") (pintype "power_in"))
      (node (ref "R223") (pin "2") (pinfunction "2_2") (pintype "passive"))
    )
    (net (code "51") (name "Net-(J19D-LOS)") (class "Default")
      (node (ref "J19") (pin "RB8") (pinfunction "LOS_RB8") (pintype "output"))
      (node (ref "R145") (pin "1") (pinfunction "1_1") (pintype "passive"))
    )
    (net (code "52") (name "Net-(J19D-MOD_DEF0)") (class "Default")
      (node (ref "J19") (pin "RB6") (pinfunction "MOD_DEF0_RB6") (pintype "output"))
      (node (ref "R174") (pin "1") (pinfunction "1_1") (pintype "passive"))
    )
    (net (code "53") (name "Net-(J19D-RATE_SELECT)") (class "Default")
      (node (ref "J19") (pin "RB7") (pinfunction "RATE_SELECT_RB7") (pintype "input"))
      (node (ref "R193") (pin "2") (pinfunction "2_2") (pintype "passive"))
    )
    (net (code "54") (name "Net-(J19D-TX_DISABLE)") (class "Default")
      (node (ref "J19") (pin "RB3") (pinfunction "TX_DISABLE_RB3") (pintype "input"))
      (node (ref "R192") (pin "2") (pinfunction "2_2") (pintype "passive"))
    )
    (net (code "55") (name "Net-(J19D-TX_FAULT)") (class "Default")
      (node (ref "J19") (pin "RB2") (pinfunction "TX_FAULT_RB2") (pintype "output"))
      (node (ref "R144") (pin "1") (pinfunction "1_1") (pintype "passive"))
    )
    (net (code "56") (name "Net-(J19D-VCCR)") (class "Default")
      (node (ref "C268") (pin "2") (pinfunction "2_2") (pintype "passive"))
      (node (ref "C269") (pin "2") (pinfunction "2_2") (pintype "passive"))
      (node (ref "C270") (pin "2") (pinfunction "2_2") (pintype "passive"))
      (node (ref "C271") (pin "2") (pinfunction "2_2") (pintype "passive"))
      (node (ref "J19") (pin "RB15") (pinfunction "VCCR_RB15") (pintype "power_in"))
      (node (ref "L32") (pin "2") (pinfunction "2_2") (pintype "passive"))
    )
    (net (code "57") (name "Net-(J19D-VCCT)") (class "Default")
      (node (ref "C272") (pin "2") (pinfunction "2_2") (pintype "passive"))
      (node (ref "C273") (pin "2") (pinfunction "2_2") (pintype "passive"))
      (node (ref "J19") (pin "RB16") (pinfunction "VCCT_RB16") (pintype "power_in"))
      (node (ref "L33") (pin "2") (pinfunction "2_2") (pintype "passive"))
    )
    (net (code "58") (name "Net-(J19D-VEER-PadRB9)") (class "Default")
      (node (ref "J19") (pin "RB9") (pinfunction "VEER_RB9") (pintype "power_in"))
      (node (ref "R215") (pin "2") (pinfunction "2_2") (pintype "passive"))
    )
    (net (code "59") (name "Net-(LD11-C)") (class "Default")
      (node (ref "LD11") (pin "1") (pinfunction "C_1") (pintype "passive"))
      (node (ref "R143") (pin "2") (pinfunction "2_2") (pintype "passive"))
    )
    (net (code "60") (name "Net-(LD15-C)") (class "Default")
      (node (ref "LD15") (pin "1") (pinfunction "C_1") (pintype "passive"))
      (node (ref "R142") (pin "2") (pinfunction "2_2") (pintype "passive"))
    )
    (net (code "61") (name "Net-(LD16-C)") (class "Default")
      (node (ref "LD16") (pin "1") (pinfunction "C_1") (pintype "passive"))
      (node (ref "R216") (pin "2") (pinfunction "2_2") (pintype "passive"))
    )
    (net (code "62") (name "Net-(LD17-C)") (class "Default")
      (node (ref "LD17") (pin "1") (pinfunction "C_1") (pintype "passive"))
      (node (ref "R220") (pin "2") (pinfunction "2_2") (pintype "passive"))
    )
    (net (code "63") (name "Net-(T11-D)") (class "Default")
      (node (ref "R143") (pin "1") (pinfunction "1_1") (pintype "passive"))
      (node (ref "T11") (pin "3") (pinfunction "D_3") (pintype "passive"))
    )
    (net (code "64") (name "Net-(T16-D)") (class "Default")
      (node (ref "R142") (pin "1") (pinfunction "1_1") (pintype "passive"))
      (node (ref "T16") (pin "3") (pinfunction "D_3") (pintype "passive"))
    )
    (net (code "65") (name "Net-(T17-D)") (class "Default")
      (node (ref "R216") (pin "1") (pinfunction "1_1") (pintype "passive"))
      (node (ref "T17") (pin "3") (pinfunction "D_3") (pintype "passive"))
    )
    (net (code "66") (name "Net-(T18-D)") (class "Default")
      (node (ref "R220") (pin "1") (pinfunction "1_1") (pintype "passive"))
      (node (ref "T18") (pin "3") (pinfunction "D_3") (pintype "passive"))
    )
    (net (code "67") (name "P3V3") (class "Default")
      (node (ref "C160") (pin "2") (pinfunction "2_2") (pintype "passive"))
      (node (ref "C178") (pin "2") (pinfunction "2_2") (pintype "passive"))
      (node (ref "C181") (pin "2") (pinfunction "2_2") (pintype "passive"))
      (node (ref "C244") (pin "2") (pinfunction "2_2") (pintype "passive"))
      (node (ref "C258") (pin "2") (pinfunction "2_2") (pintype "passive"))
      (node (ref "C259") (pin "2") (pinfunction "2_2") (pintype "passive"))
      (node (ref "C266") (pin "2") (pinfunction "2_2") (pintype "passive"))
      (node (ref "C267") (pin "2") (pinfunction "2_2") (pintype "passive"))
      (node (ref "L19") (pin "1") (pinfunction "1_1") (pintype "passive"))
      (node (ref "L20") (pin "1") (pinfunction "1_1") (pintype "passive"))
      (node (ref "L21") (pin "1") (pinfunction "1_1") (pintype "passive"))
      (node (ref "L30") (pin "1") (pinfunction "1_1") (pintype "passive"))
      (node (ref "L31") (pin "1") (pinfunction "1_1") (pintype "passive"))
      (node (ref "L32") (pin "1") (pinfunction "1_1") (pintype "passive"))
      (node (ref "L33") (pin "1") (pinfunction "1_1") (pintype "passive"))
      (node (ref "L34") (pin "1") (pinfunction "1_1") (pintype "passive"))
      (node (ref "LD11") (pin "2") (pinfunction "A_2") (pintype "passive"))
      (node (ref "LD15") (pin "2") (pinfunction "A_2") (pintype "passive"))
      (node (ref "LD16") (pin "2") (pinfunction "A_2") (pintype "passive"))
      (node (ref "LD17") (pin "2") (pinfunction "A_2") (pintype "passive"))
      (node (ref "R133") (pin "2") (pinfunction "2_2") (pintype "passive"))
      (node (ref "R134") (pin "2") (pinfunction "2_2") (pintype "passive"))
      (node (ref "R135") (pin "2") (pinfunction "2_2") (pintype "passive"))
      (node (ref "R136") (pin "2") (pinfunction "2_2") (pintype "passive"))
      (node (ref "R137") (pin "2") (pinfunction "2_2") (pintype "passive"))
      (node (ref "R138") (pin "2") (pinfunction "2_2") (pintype "passive"))
      (node (ref "R144") (pin "2") (pinfunction "2_2") (pintype "passive"))
      (node (ref "R145") (pin "2") (pinfunction "2_2") (pintype "passive"))
      (node (ref "R174") (pin "2") (pinfunction "2_2") (pintype "passive"))
      (node (ref "R217") (pin "2") (pinfunction "2_2") (pintype "passive"))
      (node (ref "R218") (pin "2") (pinfunction "2_2") (pintype "passive"))
      (node (ref "R219") (pin "2") (pinfunction "2_2") (pintype "passive"))
    )
    (net (code "68") (name "unconnected-(J19A-MOD_DEF1-PadLT5)") (class "Default")
      (node (ref "J19") (pin "LT5") (pinfunction "MOD_DEF1_LT5") (pintype "input"))
    )
    (net (code "69") (name "unconnected-(J19A-MOD_DEF2-PadLT4)") (class "Default")
      (node (ref "J19") (pin "LT4") (pinfunction "MOD_DEF2_LT4") (pintype "bidirectional"))
    )
    (net (code "70") (name "unconnected-(J19B-MOD_DEF1-PadLB5)") (class "Default")
      (node (ref "J19") (pin "LB5") (pinfunction "MOD_DEF1_LB5") (pintype "input"))
    )
    (net (code "71") (name "unconnected-(J19B-MOD_DEF2-PadLB4)") (class "Default")
      (node (ref "J19") (pin "LB4") (pinfunction "MOD_DEF2_LB4") (pintype "bidirectional"))
    )
    (net (code "72") (name "unconnected-(J19C-MOD_DEF1-PadRT5)") (class "Default")
      (node (ref "J19") (pin "RT5") (pinfunction "MOD_DEF1_RT5") (pintype "input"))
    )
    (net (code "73") (name "unconnected-(J19C-MOD_DEF2-PadRT4)") (class "Default")
      (node (ref "J19") (pin "RT4") (pinfunction "MOD_DEF2_RT4") (pintype "bidirectional"))
    )
    (net (code "74") (name "unconnected-(J19D-MOD_DEF1-PadRB5)") (class "Default")
      (node (ref "J19") (pin "RB5") (pinfunction "MOD_DEF1_RB5") (pintype "input"))
    )
    (net (code "75") (name "unconnected-(J19D-MOD_DEF2-PadRB4)") (class "Default")
      (node (ref "J19") (pin "RB4") (pinfunction "MOD_DEF2_RB4") (pintype "bidirectional"))
    )
  )
)
